# Robot.net
KiCad netlist of a schematic drawn in EAGLE
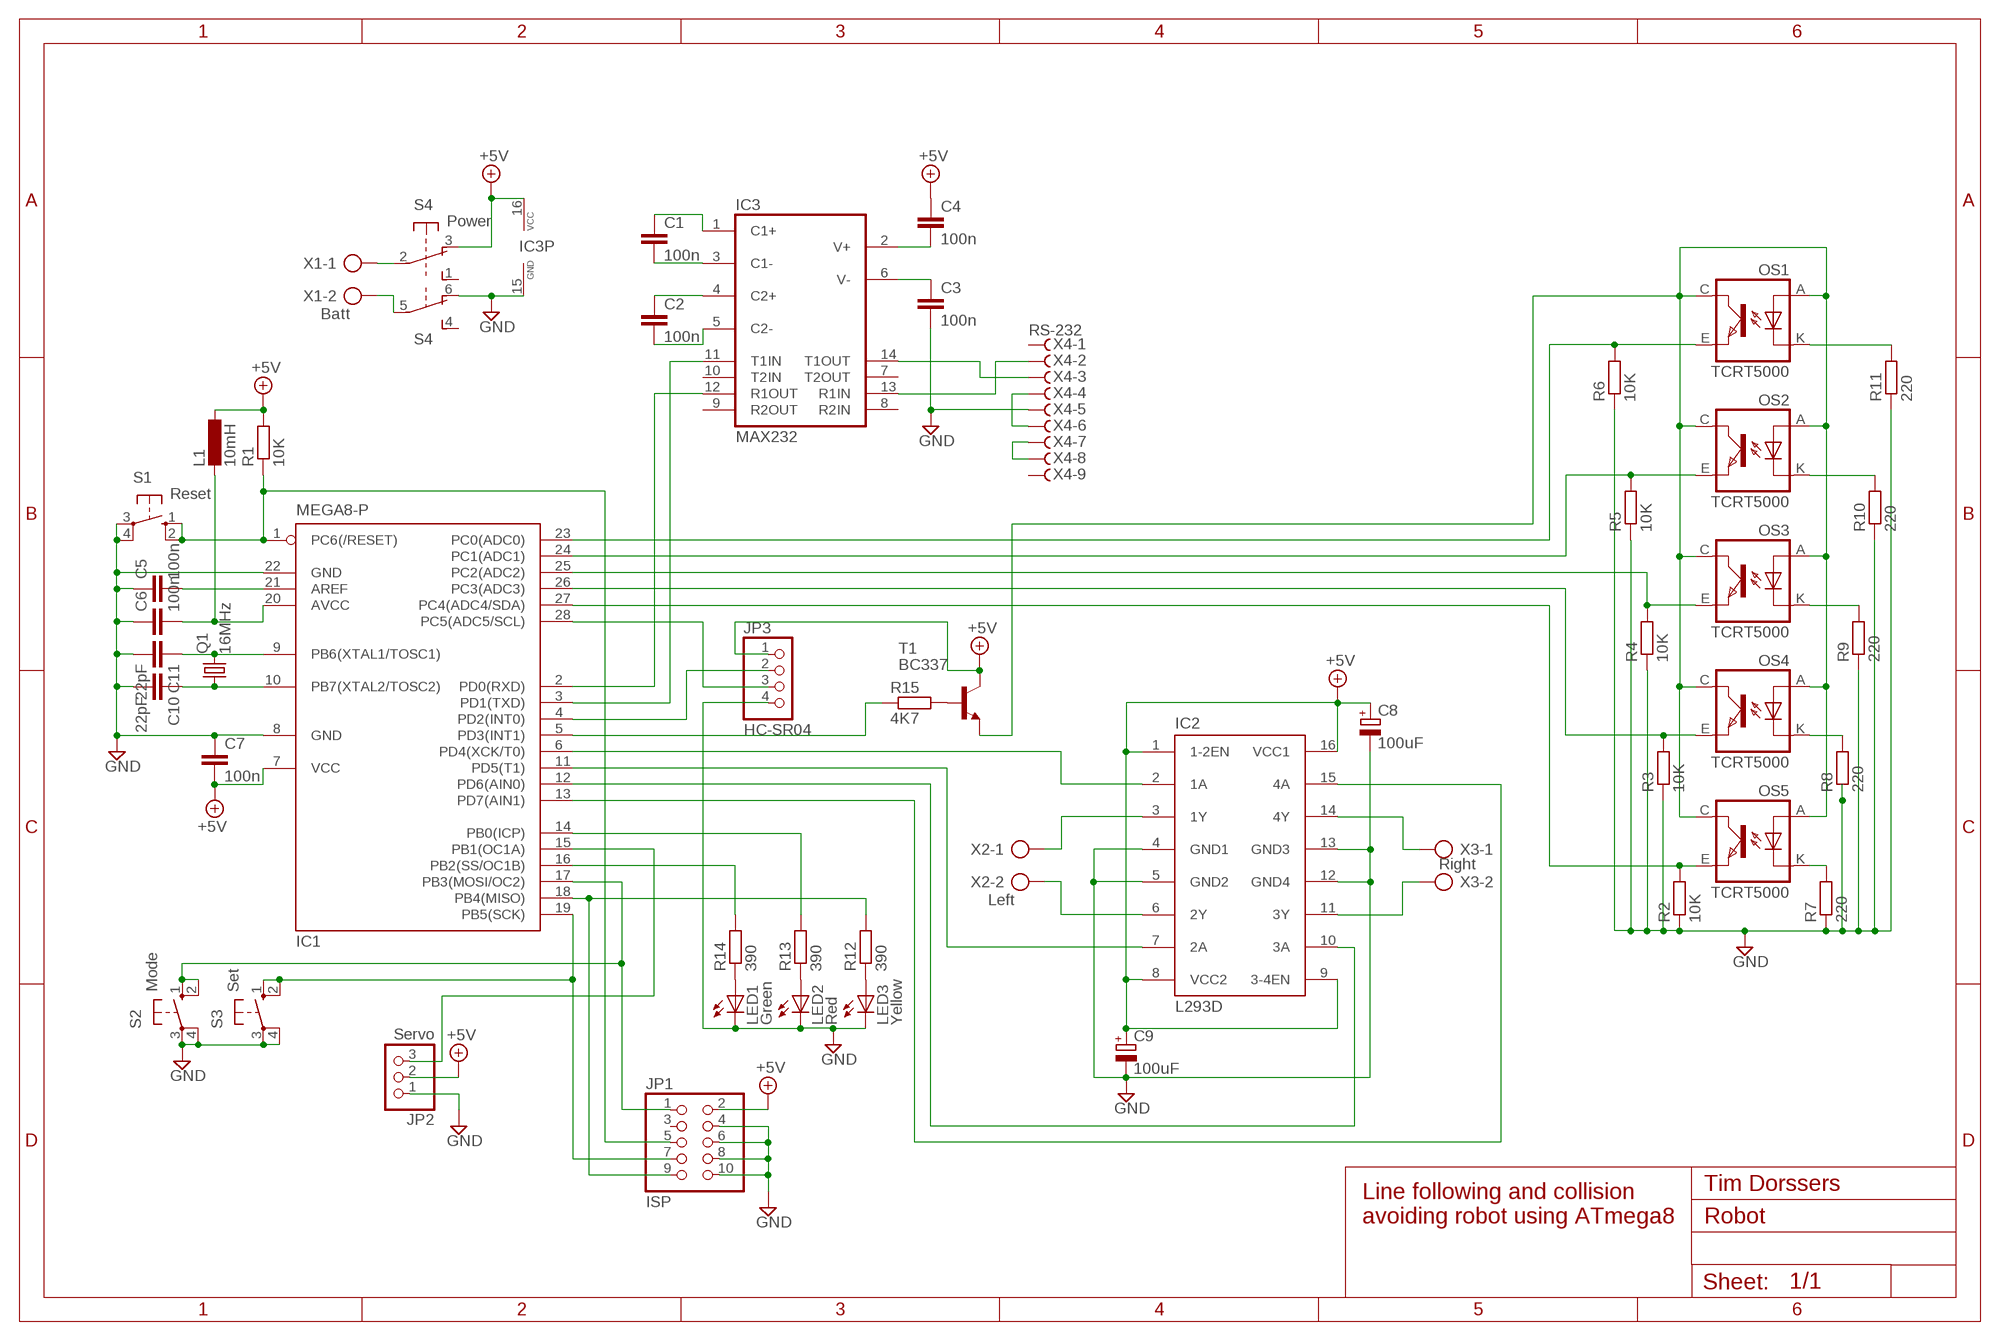
[diagram p0: schematic, sheet 1]

(export (version "E")
  (design (tool "Eeschema 10.0.6"))
  (components
    (comp (ref "C1")
      (value "100n")
      (footprint "eagle-import:C025-025X050")
      (libsource (lib "eagle-import") (part "C-EU025-025X050"))
    )
    (comp (ref "C2")
      (value "100n")
      (footprint "eagle-import:C025-025X050")
      (libsource (lib "eagle-import") (part "C-EU025-025X050"))
    )
    (comp (ref "C3")
      (value "100n")
      (footprint "eagle-import:C025-025X050")
      (libsource (lib "eagle-import") (part "C-EU025-025X050"))
    )
    (comp (ref "C4")
      (value "100n")
      (footprint "eagle-import:C025-025X050")
      (libsource (lib "eagle-import") (part "C-EU025-025X050"))
    )
    (comp (ref "C5")
      (value "100n")
      (footprint "eagle-import:C025-025X050")
      (libsource (lib "eagle-import") (part "C-EU025-025X050"))
    )
    (comp (ref "C6")
      (value "100n")
      (footprint "eagle-import:C025-025X050")
      (libsource (lib "eagle-import") (part "C-EU025-025X050"))
    )
    (comp (ref "C7")
      (value "100n")
      (footprint "eagle-import:C025-025X050")
      (libsource (lib "eagle-import") (part "C-EU025-025X050"))
    )
    (comp (ref "C8")
      (value "100uF")
      (footprint "eagle-import:B45181A")
      (libsource (lib "eagle-import") (part "CPOL-EUB45181A"))
    )
    (comp (ref "C9")
      (value "100uF")
      (footprint "eagle-import:B45181A")
      (libsource (lib "eagle-import") (part "CPOL-EUB45181A"))
    )
    (comp (ref "C10")
      (value "22pF")
      (footprint "eagle-import:C025-024X044")
      (libsource (lib "eagle-import") (part "C-EU025-024X044"))
    )
    (comp (ref "C11")
      (value "22pF")
      (footprint "eagle-import:C025-024X044")
      (libsource (lib "eagle-import") (part "C-EU025-024X044"))
    )
    (comp (ref "IC1")
      (value "MEGA8-P")
      (footprint "eagle-import:DIL28-3")
      (libsource (lib "eagle-import") (part "MEGA8-P"))
    )
    (comp (ref "IC2")
      (value "L293D")
      (footprint "eagle-import:DIL16")
      (libsource (lib "eagle-import") (part "L293D"))
    )
    (comp (ref "IC3")
      (value "MAX232")
      (footprint "eagle-import:DIL16")
      (libsource (lib "eagle-import") (part "MAX232"))
    )
    (comp (ref "JP1")
      (value "ISP")
      (footprint "eagle-import:2X05")
      (libsource (lib "eagle-import") (part "PINHD-2X5"))
    )
    (comp (ref "JP2")
      (value "Servo")
      (footprint "eagle-import:1X03")
      (libsource (lib "eagle-import") (part "PINHD-1X3"))
    )
    (comp (ref "JP3")
      (value "HC-SR04")
      (footprint "eagle-import:1X04")
      (libsource (lib "eagle-import") (part "PINHD-1X4"))
    )
    (comp (ref "L1")
      (value "10mH")
      (footprint "eagle-import:0207_10")
      (libsource (lib "eagle-import") (part "L-EU0207/10"))
    )
    (comp (ref "LED1")
      (value "Green")
      (footprint "eagle-import:LED5MM")
      (libsource (lib "eagle-import") (part "LED5MM"))
    )
    (comp (ref "LED2")
      (value "Red")
      (footprint "eagle-import:LED5MM")
      (libsource (lib "eagle-import") (part "LED5MM"))
    )
    (comp (ref "LED3")
      (value "Yellow")
      (footprint "eagle-import:LED5MM")
      (libsource (lib "eagle-import") (part "LED5MM"))
    )
    (comp (ref "OS1")
      (value "TCRT5000")
      (footprint "eagle-import:TCRT5000")
      (libsource (lib "eagle-import") (part "TCRT5000"))
    )
    (comp (ref "OS2")
      (value "TCRT5000")
      (footprint "eagle-import:TCRT5000")
      (libsource (lib "eagle-import") (part "TCRT5000"))
    )
    (comp (ref "OS3")
      (value "TCRT5000")
      (footprint "eagle-import:TCRT5000")
      (libsource (lib "eagle-import") (part "TCRT5000"))
    )
    (comp (ref "OS4")
      (value "TCRT5000")
      (footprint "eagle-import:TCRT5000")
      (libsource (lib "eagle-import") (part "TCRT5000"))
    )
    (comp (ref "OS5")
      (value "TCRT5000")
      (footprint "eagle-import:TCRT5000")
      (libsource (lib "eagle-import") (part "TCRT5000"))
    )
    (comp (ref "Q1")
      (value "16MHz")
      (footprint "eagle-import:HC49U-V")
      (libsource (lib "eagle-import") (part "CRYSTALHC49U-V"))
    )
    (comp (ref "R1")
      (value "10K")
      (footprint "eagle-import:0204_7")
      (libsource (lib "eagle-import") (part "R-EU_0204/7"))
    )
    (comp (ref "R2")
      (value "10K")
      (footprint "eagle-import:0204_7")
      (libsource (lib "eagle-import") (part "R-EU_0204/7"))
    )
    (comp (ref "R3")
      (value "10K")
      (footprint "eagle-import:0204_7")
      (libsource (lib "eagle-import") (part "R-EU_0204/7"))
    )
    (comp (ref "R4")
      (value "10K")
      (footprint "eagle-import:0204_7")
      (libsource (lib "eagle-import") (part "R-EU_0204/7"))
    )
    (comp (ref "R5")
      (value "10K")
      (footprint "eagle-import:0204_7")
      (libsource (lib "eagle-import") (part "R-EU_0204/7"))
    )
    (comp (ref "R6")
      (value "10K")
      (footprint "eagle-import:0204_7")
      (libsource (lib "eagle-import") (part "R-EU_0204/7"))
    )
    (comp (ref "R7")
      (value "220")
      (footprint "eagle-import:0204_7")
      (libsource (lib "eagle-import") (part "R-EU_0204/7"))
    )
    (comp (ref "R8")
      (value "220")
      (footprint "eagle-import:0204_7")
      (libsource (lib "eagle-import") (part "R-EU_0204/7"))
    )
    (comp (ref "R9")
      (value "220")
      (footprint "eagle-import:0204_7")
      (libsource (lib "eagle-import") (part "R-EU_0204/7"))
    )
    (comp (ref "R10")
      (value "220")
      (footprint "eagle-import:0204_7")
      (libsource (lib "eagle-import") (part "R-EU_0204/7"))
    )
    (comp (ref "R11")
      (value "220")
      (footprint "eagle-import:0204_7")
      (libsource (lib "eagle-import") (part "R-EU_0204/7"))
    )
    (comp (ref "R12")
      (value "390")
      (footprint "eagle-import:0204_7")
      (libsource (lib "eagle-import") (part "R-EU_0204/7"))
    )
    (comp (ref "R13")
      (value "390")
      (footprint "eagle-import:0204_7")
      (libsource (lib "eagle-import") (part "R-EU_0204/7"))
    )
    (comp (ref "R14")
      (value "390")
      (footprint "eagle-import:0204_7")
      (libsource (lib "eagle-import") (part "R-EU_0204/7"))
    )
    (comp (ref "R15")
      (value "4K7")
      (footprint "eagle-import:0204_7")
      (libsource (lib "eagle-import") (part "R-EU_0204/7"))
    )
    (comp (ref "S1")
      (value "Reset")
      (footprint "eagle-import:B3F-10XX")
      (fields (field (name "MPN") "B3F-1000"))
      (libsource (lib "eagle-import") (part "10-XX"))
    )
    (comp (ref "S2")
      (value "Mode")
      (footprint "eagle-import:B3F-10XX")
      (fields (field (name "MPN") "B3F-1000"))
      (libsource (lib "eagle-import") (part "10-XX"))
    )
    (comp (ref "S3")
      (value "Set")
      (footprint "eagle-import:B3F-10XX")
      (fields (field (name "MPN") "B3F-1000"))
      (libsource (lib "eagle-import") (part "10-XX"))
    )
    (comp (ref "S4")
      (value "Power")
      (footprint "eagle-import:PVA2F")
      (libsource (lib "eagle-import") (part "PVA2"))
    )
    (comp (ref "T1")
      (value "BC337")
      (footprint "eagle-import:TO92")
      (libsource (lib "eagle-import") (part "BC337"))
    )
    (comp (ref "X1")
      (value "Batt")
      (footprint "eagle-import:AK300_2")
      (libsource (lib "eagle-import") (part "AK300/2"))
    )
    (comp (ref "X2")
      (value "Left")
      (footprint "eagle-import:AK300_2")
      (libsource (lib "eagle-import") (part "AK300/2"))
    )
    (comp (ref "X3")
      (value "Right")
      (footprint "eagle-import:AK300_2")
      (libsource (lib "eagle-import") (part "AK300/2"))
    )
    (comp (ref "X4")
      (value "RS-232")
      (footprint "eagle-import:H3M09RA")
      (libsource (lib "eagle-import") (part "D-SUB9-H3M09RA"))
    )
  )
  (nets
    (net (code "1") (name "+5V") (class "Default")
      (node (ref "C4") (pin "1") (pinfunction "1_1") (pintype "passive"))
      (node (ref "C7") (pin "2") (pinfunction "2_2") (pintype "passive"))
      (node (ref "C8") (pin "+") (pinfunction "+_+") (pintype "passive"))
      (node (ref "C9") (pin "+") (pinfunction "+_+") (pintype "passive"))
      (node (ref "IC1") (pin "7") (pinfunction "VCC_7") (pintype "power_in"))
      (node (ref "IC2") (pin "1") (pinfunction "1-2EN_1") (pintype "input"))
      (node (ref "IC2") (pin "16") (pinfunction "VCC1_16") (pintype "power_in"))
      (node (ref "IC2") (pin "8") (pinfunction "VCC2_8") (pintype "power_in"))
      (node (ref "IC2") (pin "9") (pinfunction "3-4EN_9") (pintype "input"))
      (node (ref "IC3") (pin "16") (pinfunction "VCC_16") (pintype "power_in"))
      (node (ref "JP1") (pin "2") (pinfunction "2_2") (pintype "passive"))
      (node (ref "JP2") (pin "2") (pinfunction "2_2") (pintype "passive"))
      (node (ref "JP3") (pin "1") (pinfunction "1_1") (pintype "passive"))
      (node (ref "L1") (pin "1") (pinfunction "1_1") (pintype "passive"))
      (node (ref "R1") (pin "2") (pinfunction "2_2") (pintype "passive"))
      (node (ref "S4") (pin "3") (pinfunction "O_3") (pintype "passive"))
      (node (ref "T1") (pin "3") (pinfunction "C_3") (pintype "passive"))
    )
    (net (code "2") (name "GND") (class "Default")
      (node (ref "C10") (pin "2") (pinfunction "2_2") (pintype "passive"))
      (node (ref "C11") (pin "2") (pinfunction "2_2") (pintype "passive"))
      (node (ref "C3") (pin "2") (pinfunction "2_2") (pintype "passive"))
      (node (ref "C5") (pin "1") (pinfunction "1_1") (pintype "passive"))
      (node (ref "C6") (pin "1") (pinfunction "1_1") (pintype "passive"))
      (node (ref "C7") (pin "1") (pinfunction "1_1") (pintype "passive"))
      (node (ref "C8") (pin "-") (pinfunction "-_-") (pintype "passive"))
      (node (ref "C9") (pin "-") (pinfunction "-_-") (pintype "passive"))
      (node (ref "IC1") (pin "22") (pinfunction "GND_22") (pintype "power_in"))
      (node (ref "IC1") (pin "8") (pinfunction "GND_8") (pintype "power_in"))
      (node (ref "IC2") (pin "12") (pinfunction "GND4_12") (pintype "power_in"))
      (node (ref "IC2") (pin "13") (pinfunction "GND3_13") (pintype "power_in"))
      (node (ref "IC2") (pin "4") (pinfunction "GND1_4") (pintype "power_in"))
      (node (ref "IC2") (pin "5") (pinfunction "GND2_5") (pintype "power_in"))
      (node (ref "IC3") (pin "15") (pinfunction "GND_15") (pintype "power_in"))
      (node (ref "JP1") (pin "10") (pinfunction "10_10") (pintype "passive"))
      (node (ref "JP1") (pin "4") (pinfunction "4_4") (pintype "passive"))
      (node (ref "JP1") (pin "6") (pinfunction "6_6") (pintype "passive"))
      (node (ref "JP1") (pin "8") (pinfunction "8_8") (pintype "passive"))
      (node (ref "JP2") (pin "1") (pinfunction "1_1") (pintype "passive"))
      (node (ref "JP3") (pin "4") (pinfunction "4_4") (pintype "passive"))
      (node (ref "LED1") (pin "K") (pinfunction "C_K") (pintype "passive"))
      (node (ref "LED2") (pin "K") (pinfunction "C_K") (pintype "passive"))
      (node (ref "LED3") (pin "K") (pinfunction "C_K") (pintype "passive"))
      (node (ref "R10") (pin "1") (pinfunction "1_1") (pintype "passive"))
      (node (ref "R11") (pin "1") (pinfunction "1_1") (pintype "passive"))
      (node (ref "R2") (pin "1") (pinfunction "1_1") (pintype "passive"))
      (node (ref "R3") (pin "1") (pinfunction "1_1") (pintype "passive"))
      (node (ref "R4") (pin "1") (pinfunction "1_1") (pintype "passive"))
      (node (ref "R5") (pin "1") (pinfunction "1_1") (pintype "passive"))
      (node (ref "R6") (pin "1") (pinfunction "1_1") (pintype "passive"))
      (node (ref "R7") (pin "1") (pinfunction "1_1") (pintype "passive"))
      (node (ref "R8") (pin "1") (pinfunction "1_1") (pintype "passive"))
      (node (ref "R9") (pin "1") (pinfunction "1_1") (pintype "passive"))
      (node (ref "S1") (pin "3") (pinfunction "P_3") (pintype "passive"))
      (node (ref "S1") (pin "4") (pinfunction "P1_4") (pintype "passive"))
      (node (ref "S2") (pin "3") (pinfunction "P_3") (pintype "passive"))
      (node (ref "S2") (pin "4") (pinfunction "P1_4") (pintype "passive"))
      (node (ref "S3") (pin "3") (pinfunction "P_3") (pintype "passive"))
      (node (ref "S3") (pin "4") (pinfunction "P1_4") (pintype "passive"))
      (node (ref "S4") (pin "6") (pinfunction "O_6") (pintype "passive"))
      (node (ref "X4") (pin "5") (pinfunction "F_5") (pintype "passive"))
    )
    (net (code "3") (name "Net-(IC1-AREF)") (class "Default")
      (node (ref "C5") (pin "2") (pinfunction "2_2") (pintype "passive"))
      (node (ref "IC1") (pin "21") (pinfunction "AREF_21") (pintype "passive"))
    )
    (net (code "4") (name "Net-(IC1-AVCC)") (class "Default")
      (node (ref "C6") (pin "2") (pinfunction "2_2") (pintype "passive"))
      (node (ref "IC1") (pin "20") (pinfunction "AVCC_20") (pintype "power_in"))
      (node (ref "L1") (pin "2") (pinfunction "2_2") (pintype "passive"))
    )
    (net (code "5") (name "Net-(IC1-PB0(ICP))") (class "Default")
      (node (ref "IC1") (pin "14") (pinfunction "PB0(ICP)_14") (pintype "bidirectional"))
      (node (ref "R13") (pin "2") (pinfunction "2_2") (pintype "passive"))
    )
    (net (code "6") (name "Net-(IC1-PB1(OC1A))") (class "Default")
      (node (ref "IC1") (pin "15") (pinfunction "PB1(OC1A)_15") (pintype "bidirectional"))
      (node (ref "JP2") (pin "3") (pinfunction "3_3") (pintype "passive"))
    )
    (net (code "7") (name "Net-(IC1-PB2(SS{slash}OC1B))") (class "Default")
      (node (ref "IC1") (pin "16") (pinfunction "PB2(SS/OC1B)_16") (pintype "bidirectional"))
      (node (ref "R14") (pin "2") (pinfunction "2_2") (pintype "passive"))
    )
    (net (code "8") (name "Net-(IC1-PB3(MOSI{slash}OC2))") (class "Default")
      (node (ref "IC1") (pin "17") (pinfunction "PB3(MOSI/OC2)_17") (pintype "bidirectional"))
      (node (ref "JP1") (pin "1") (pinfunction "1_1") (pintype "passive"))
      (node (ref "S2") (pin "1") (pinfunction "S_1") (pintype "passive"))
      (node (ref "S2") (pin "2") (pinfunction "S1_2") (pintype "passive"))
    )
    (net (code "9") (name "Net-(IC1-PB4(MISO))") (class "Default")
      (node (ref "IC1") (pin "18") (pinfunction "PB4(MISO)_18") (pintype "bidirectional"))
      (node (ref "JP1") (pin "9") (pinfunction "9_9") (pintype "passive"))
      (node (ref "R12") (pin "2") (pinfunction "2_2") (pintype "passive"))
    )
    (net (code "10") (name "Net-(IC1-PB5(SCK))") (class "Default")
      (node (ref "IC1") (pin "19") (pinfunction "PB5(SCK)_19") (pintype "bidirectional"))
      (node (ref "JP1") (pin "7") (pinfunction "7_7") (pintype "passive"))
      (node (ref "S3") (pin "1") (pinfunction "S_1") (pintype "passive"))
      (node (ref "S3") (pin "2") (pinfunction "S1_2") (pintype "passive"))
    )
    (net (code "11") (name "Net-(IC1-PB6(XTAL1{slash}TOSC1))") (class "Default")
      (node (ref "C11") (pin "1") (pinfunction "1_1") (pintype "passive"))
      (node (ref "IC1") (pin "9") (pinfunction "PB6(XTAL1/TOSC1)_9") (pintype "bidirectional"))
      (node (ref "Q1") (pin "2") (pinfunction "2_2") (pintype "passive"))
    )
    (net (code "12") (name "Net-(IC1-PB7(XTAL2{slash}TOSC2))") (class "Default")
      (node (ref "C10") (pin "1") (pinfunction "1_1") (pintype "passive"))
      (node (ref "IC1") (pin "10") (pinfunction "PB7(XTAL2/TOSC2)_10") (pintype "bidirectional"))
      (node (ref "Q1") (pin "1") (pinfunction "1_1") (pintype "passive"))
    )
    (net (code "13") (name "Net-(IC1-PC0(ADC0))") (class "Default")
      (node (ref "IC1") (pin "23") (pinfunction "PC0(ADC0)_23") (pintype "bidirectional"))
      (node (ref "OS1") (pin "E") (pinfunction "EMITTER_E") (pintype "passive"))
      (node (ref "R6") (pin "2") (pinfunction "2_2") (pintype "passive"))
    )
    (net (code "14") (name "Net-(IC1-PC1(ADC1))") (class "Default")
      (node (ref "IC1") (pin "24") (pinfunction "PC1(ADC1)_24") (pintype "bidirectional"))
      (node (ref "OS2") (pin "E") (pinfunction "EMITTER_E") (pintype "passive"))
      (node (ref "R5") (pin "2") (pinfunction "2_2") (pintype "passive"))
    )
    (net (code "15") (name "Net-(IC1-PC2(ADC2))") (class "Default")
      (node (ref "IC1") (pin "25") (pinfunction "PC2(ADC2)_25") (pintype "bidirectional"))
      (node (ref "OS3") (pin "E") (pinfunction "EMITTER_E") (pintype "passive"))
      (node (ref "R4") (pin "2") (pinfunction "2_2") (pintype "passive"))
    )
    (net (code "16") (name "Net-(IC1-PC3(ADC3))") (class "Default")
      (node (ref "IC1") (pin "26") (pinfunction "PC3(ADC3)_26") (pintype "bidirectional"))
      (node (ref "OS4") (pin "E") (pinfunction "EMITTER_E") (pintype "passive"))
      (node (ref "R3") (pin "2") (pinfunction "2_2") (pintype "passive"))
    )
    (net (code "17") (name "Net-(IC1-PC4(ADC4{slash}SDA))") (class "Default")
      (node (ref "IC1") (pin "27") (pinfunction "PC4(ADC4/SDA)_27") (pintype "bidirectional"))
      (node (ref "OS5") (pin "E") (pinfunction "EMITTER_E") (pintype "passive"))
      (node (ref "R2") (pin "2") (pinfunction "2_2") (pintype "passive"))
    )
    (net (code "18") (name "Net-(IC1-PC5(ADC5{slash}SCL))") (class "Default")
      (node (ref "IC1") (pin "28") (pinfunction "PC5(ADC5/SCL)_28") (pintype "bidirectional"))
      (node (ref "JP3") (pin "3") (pinfunction "3_3") (pintype "passive"))
    )
    (net (code "19") (name "Net-(IC1-PC6({slash}RESET))") (class "Default")
      (node (ref "IC1") (pin "1") (pinfunction "PC6(/RESET)_1") (pintype "bidirectional"))
      (node (ref "JP1") (pin "5") (pinfunction "5_5") (pintype "passive"))
      (node (ref "R1") (pin "1") (pinfunction "1_1") (pintype "passive"))
      (node (ref "S1") (pin "1") (pinfunction "S_1") (pintype "passive"))
      (node (ref "S1") (pin "2") (pinfunction "S1_2") (pintype "passive"))
    )
    (net (code "20") (name "Net-(IC1-PD0(RXD))") (class "Default")
      (node (ref "IC1") (pin "2") (pinfunction "PD0(RXD)_2") (pintype "bidirectional"))
      (node (ref "IC3") (pin "12") (pinfunction "R1OUT_12") (pintype "output"))
    )
    (net (code "21") (name "Net-(IC1-PD1(TXD))") (class "Default")
      (node (ref "IC1") (pin "3") (pinfunction "PD1(TXD)_3") (pintype "bidirectional"))
      (node (ref "IC3") (pin "11") (pinfunction "T1IN_11") (pintype "input"))
    )
    (net (code "22") (name "Net-(IC1-PD2(INT0))") (class "Default")
      (node (ref "IC1") (pin "4") (pinfunction "PD2(INT0)_4") (pintype "bidirectional"))
      (node (ref "JP3") (pin "2") (pinfunction "2_2") (pintype "passive"))
    )
    (net (code "23") (name "Net-(IC1-PD3(INT1))") (class "Default")
      (node (ref "IC1") (pin "5") (pinfunction "PD3(INT1)_5") (pintype "bidirectional"))
      (node (ref "R15") (pin "1") (pinfunction "1_1") (pintype "passive"))
    )
    (net (code "24") (name "Net-(IC1-PD4(XCK{slash}T0))") (class "Default")
      (node (ref "IC1") (pin "6") (pinfunction "PD4(XCK/T0)_6") (pintype "bidirectional"))
      (node (ref "IC2") (pin "2") (pinfunction "1A_2") (pintype "input"))
    )
    (net (code "25") (name "Net-(IC1-PD5(T1))") (class "Default")
      (node (ref "IC1") (pin "11") (pinfunction "PD5(T1)_11") (pintype "bidirectional"))
      (node (ref "IC2") (pin "7") (pinfunction "2A_7") (pintype "input"))
    )
    (net (code "26") (name "Net-(IC1-PD6(AIN0))") (class "Default")
      (node (ref "IC1") (pin "12") (pinfunction "PD6(AIN0)_12") (pintype "bidirectional"))
      (node (ref "IC2") (pin "10") (pinfunction "3A_10") (pintype "input"))
    )
    (net (code "27") (name "Net-(IC1-PD7(AIN1))") (class "Default")
      (node (ref "IC1") (pin "13") (pinfunction "PD7(AIN1)_13") (pintype "bidirectional"))
      (node (ref "IC2") (pin "15") (pinfunction "4A_15") (pintype "input"))
    )
    (net (code "28") (name "Net-(IC2-1Y)") (class "Default")
      (node (ref "IC2") (pin "3") (pinfunction "1Y_3") (pintype "output"))
      (node (ref "X2") (pin "1") (pinfunction "KL_1") (pintype "passive"))
    )
    (net (code "29") (name "Net-(IC2-2Y)") (class "Default")
      (node (ref "IC2") (pin "6") (pinfunction "2Y_6") (pintype "output"))
      (node (ref "X2") (pin "2") (pinfunction "KL_2") (pintype "passive"))
    )
    (net (code "30") (name "Net-(IC2-3Y)") (class "Default")
      (node (ref "IC2") (pin "11") (pinfunction "3Y_11") (pintype "output"))
      (node (ref "X3") (pin "2") (pinfunction "KL_2") (pintype "passive"))
    )
    (net (code "31") (name "Net-(IC2-4Y)") (class "Default")
      (node (ref "IC2") (pin "14") (pinfunction "4Y_14") (pintype "output"))
      (node (ref "X3") (pin "1") (pinfunction "KL_1") (pintype "passive"))
    )
    (net (code "32") (name "Net-(IC3A-C1+)") (class "Default")
      (node (ref "C1") (pin "1") (pinfunction "1_1") (pintype "passive"))
      (node (ref "IC3") (pin "1") (pinfunction "C1+_1") (pintype "bidirectional"))
    )
    (net (code "33") (name "Net-(IC3A-C1-)") (class "Default")
      (node (ref "C1") (pin "2") (pinfunction "2_2") (pintype "passive"))
      (node (ref "IC3") (pin "3") (pinfunction "C1-_3") (pintype "bidirectional"))
    )
    (net (code "34") (name "Net-(IC3A-C2+)") (class "Default")
      (node (ref "C2") (pin "1") (pinfunction "1_1") (pintype "passive"))
      (node (ref "IC3") (pin "4") (pinfunction "C2+_4") (pintype "bidirectional"))
    )
    (net (code "35") (name "Net-(IC3A-C2-)") (class "Default")
      (node (ref "C2") (pin "2") (pinfunction "2_2") (pintype "passive"))
      (node (ref "IC3") (pin "5") (pinfunction "C2-_5") (pintype "bidirectional"))
    )
    (net (code "36") (name "Net-(IC3A-R1IN)") (class "Default")
      (node (ref "IC3") (pin "13") (pinfunction "R1IN_13") (pintype "input"))
      (node (ref "X4") (pin "2") (pinfunction "F_2") (pintype "passive"))
    )
    (net (code "37") (name "Net-(IC3A-T1OUT)") (class "Default")
      (node (ref "IC3") (pin "14") (pinfunction "T1OUT_14") (pintype "output"))
      (node (ref "X4") (pin "3") (pinfunction "F_3") (pintype "passive"))
    )
    (net (code "38") (name "Net-(IC3A-V+)") (class "Default")
      (node (ref "C4") (pin "2") (pinfunction "2_2") (pintype "passive"))
      (node (ref "IC3") (pin "2") (pinfunction "V+_2") (pintype "bidirectional"))
    )
    (net (code "39") (name "Net-(IC3A-V-)") (class "Default")
      (node (ref "C3") (pin "1") (pinfunction "1_1") (pintype "passive"))
      (node (ref "IC3") (pin "6") (pinfunction "V-_6") (pintype "bidirectional"))
    )
    (net (code "40") (name "Net-(LED1-PadA)") (class "Default")
      (node (ref "LED1") (pin "A") (pinfunction "A_A") (pintype "passive"))
      (node (ref "R14") (pin "1") (pinfunction "1_1") (pintype "passive"))
    )
    (net (code "41") (name "Net-(LED2-PadA)") (class "Default")
      (node (ref "LED2") (pin "A") (pinfunction "A_A") (pintype "passive"))
      (node (ref "R13") (pin "1") (pinfunction "1_1") (pintype "passive"))
    )
    (net (code "42") (name "Net-(LED3-PadA)") (class "Default")
      (node (ref "LED3") (pin "A") (pinfunction "A_A") (pintype "passive"))
      (node (ref "R12") (pin "1") (pinfunction "1_1") (pintype "passive"))
    )
    (net (code "43") (name "Net-(OS1-ANODE)") (class "Default")
      (node (ref "OS1") (pin "A") (pinfunction "ANODE_A") (pintype "passive"))
      (node (ref "OS1") (pin "C") (pinfunction "COLLECTOR_C") (pintype "passive"))
      (node (ref "OS2") (pin "A") (pinfunction "ANODE_A") (pintype "passive"))
      (node (ref "OS2") (pin "C") (pinfunction "COLLECTOR_C") (pintype "passive"))
      (node (ref "OS3") (pin "A") (pinfunction "ANODE_A") (pintype "passive"))
      (node (ref "OS3") (pin "C") (pinfunction "COLLECTOR_C") (pintype "passive"))
      (node (ref "OS4") (pin "A") (pinfunction "ANODE_A") (pintype "passive"))
      (node (ref "OS4") (pin "C") (pinfunction "COLLECTOR_C") (pintype "passive"))
      (node (ref "OS5") (pin "A") (pinfunction "ANODE_A") (pintype "passive"))
      (node (ref "OS5") (pin "C") (pinfunction "COLLECTOR_C") (pintype "passive"))
      (node (ref "T1") (pin "1") (pinfunction "E_1") (pintype "passive"))
    )
    (net (code "44") (name "Net-(OS1-CATHODE)") (class "Default")
      (node (ref "OS1") (pin "K") (pinfunction "CATHODE_K") (pintype "passive"))
      (node (ref "R11") (pin "2") (pinfunction "2_2") (pintype "passive"))
    )
    (net (code "45") (name "Net-(OS2-CATHODE)") (class "Default")
      (node (ref "OS2") (pin "K") (pinfunction "CATHODE_K") (pintype "passive"))
      (node (ref "R10") (pin "2") (pinfunction "2_2") (pintype "passive"))
    )
    (net (code "46") (name "Net-(OS3-CATHODE)") (class "Default")
      (node (ref "OS3") (pin "K") (pinfunction "CATHODE_K") (pintype "passive"))
      (node (ref "R9") (pin "2") (pinfunction "2_2") (pintype "passive"))
    )
    (net (code "47") (name "Net-(OS4-CATHODE)") (class "Default")
      (node (ref "OS4") (pin "K") (pinfunction "CATHODE_K") (pintype "passive"))
      (node (ref "R8") (pin "2") (pinfunction "2_2") (pintype "passive"))
    )
    (net (code "48") (name "Net-(OS5-CATHODE)") (class "Default")
      (node (ref "OS5") (pin "K") (pinfunction "CATHODE_K") (pintype "passive"))
      (node (ref "R7") (pin "2") (pinfunction "2_2") (pintype "passive"))
    )
    (net (code "49") (name "Net-(S4A-P)") (class "Default")
      (node (ref "S4") (pin "2") (pinfunction "P_2") (pintype "passive"))
      (node (ref "X1") (pin "1") (pinfunction "KL_1") (pintype "passive"))
    )
    (net (code "50") (name "Net-(S4B-P)") (class "Default")
      (node (ref "S4") (pin "5") (pinfunction "P_5") (pintype "passive"))
      (node (ref "X1") (pin "2") (pinfunction "KL_2") (pintype "passive"))
    )
    (net (code "51") (name "Net-(T1-B)") (class "Default")
      (node (ref "R15") (pin "2") (pinfunction "2_2") (pintype "passive"))
      (node (ref "T1") (pin "2") (pinfunction "B_2") (pintype "passive"))
    )
    (net (code "52") (name "Net-(X4D-F)") (class "Default")
      (node (ref "X4") (pin "4") (pinfunction "F_4") (pintype "passive"))
      (node (ref "X4") (pin "6") (pinfunction "F_6") (pintype "passive"))
    )
    (net (code "53") (name "Net-(X4G-F)") (class "Default")
      (node (ref "X4") (pin "7") (pinfunction "F_7") (pintype "passive"))
      (node (ref "X4") (pin "8") (pinfunction "F_8") (pintype "passive"))
    )
    (net (code "54") (name "unconnected-(IC3A-R2IN-Pad8)") (class "Default")
      (node (ref "IC3") (pin "8") (pinfunction "R2IN_8") (pintype "input"))
    )
    (net (code "55") (name "unconnected-(IC3A-R2OUT-Pad9)") (class "Default")
      (node (ref "IC3") (pin "9") (pinfunction "R2OUT_9") (pintype "output"))
    )
    (net (code "56") (name "unconnected-(IC3A-T2IN-Pad10)") (class "Default")
      (node (ref "IC3") (pin "10") (pinfunction "T2IN_10") (pintype "input"))
    )
    (net (code "57") (name "unconnected-(IC3A-T2OUT-Pad7)") (class "Default")
      (node (ref "IC3") (pin "7") (pinfunction "T2OUT_7") (pintype "output"))
    )
    (net (code "58") (name "unconnected-(JP1-Pad3)") (class "Default")
      (node (ref "JP1") (pin "3") (pinfunction "3_3") (pintype "passive"))
    )
    (net (code "59") (name "unconnected-(S4A-S-Pad1)") (class "Default")
      (node (ref "S4") (pin "1") (pinfunction "S_1") (pintype "passive"))
    )
    (net (code "60") (name "unconnected-(S4B-S-Pad4)") (class "Default")
      (node (ref "S4") (pin "4") (pinfunction "S_4") (pintype "passive"))
    )
    (net (code "61") (name "unconnected-(X4A-F-Pad1)") (class "Default")
      (node (ref "X4") (pin "1") (pinfunction "F_1") (pintype "passive"))
    )
    (net (code "62") (name "unconnected-(X4I-F-Pad9)") (class "Default")
      (node (ref "X4") (pin "9") (pinfunction "F_9") (pintype "passive"))
    )
  )
)
